# Adafruit_Audio_BFF_PCB.net
KiCad netlist of a schematic drawn in EAGLE
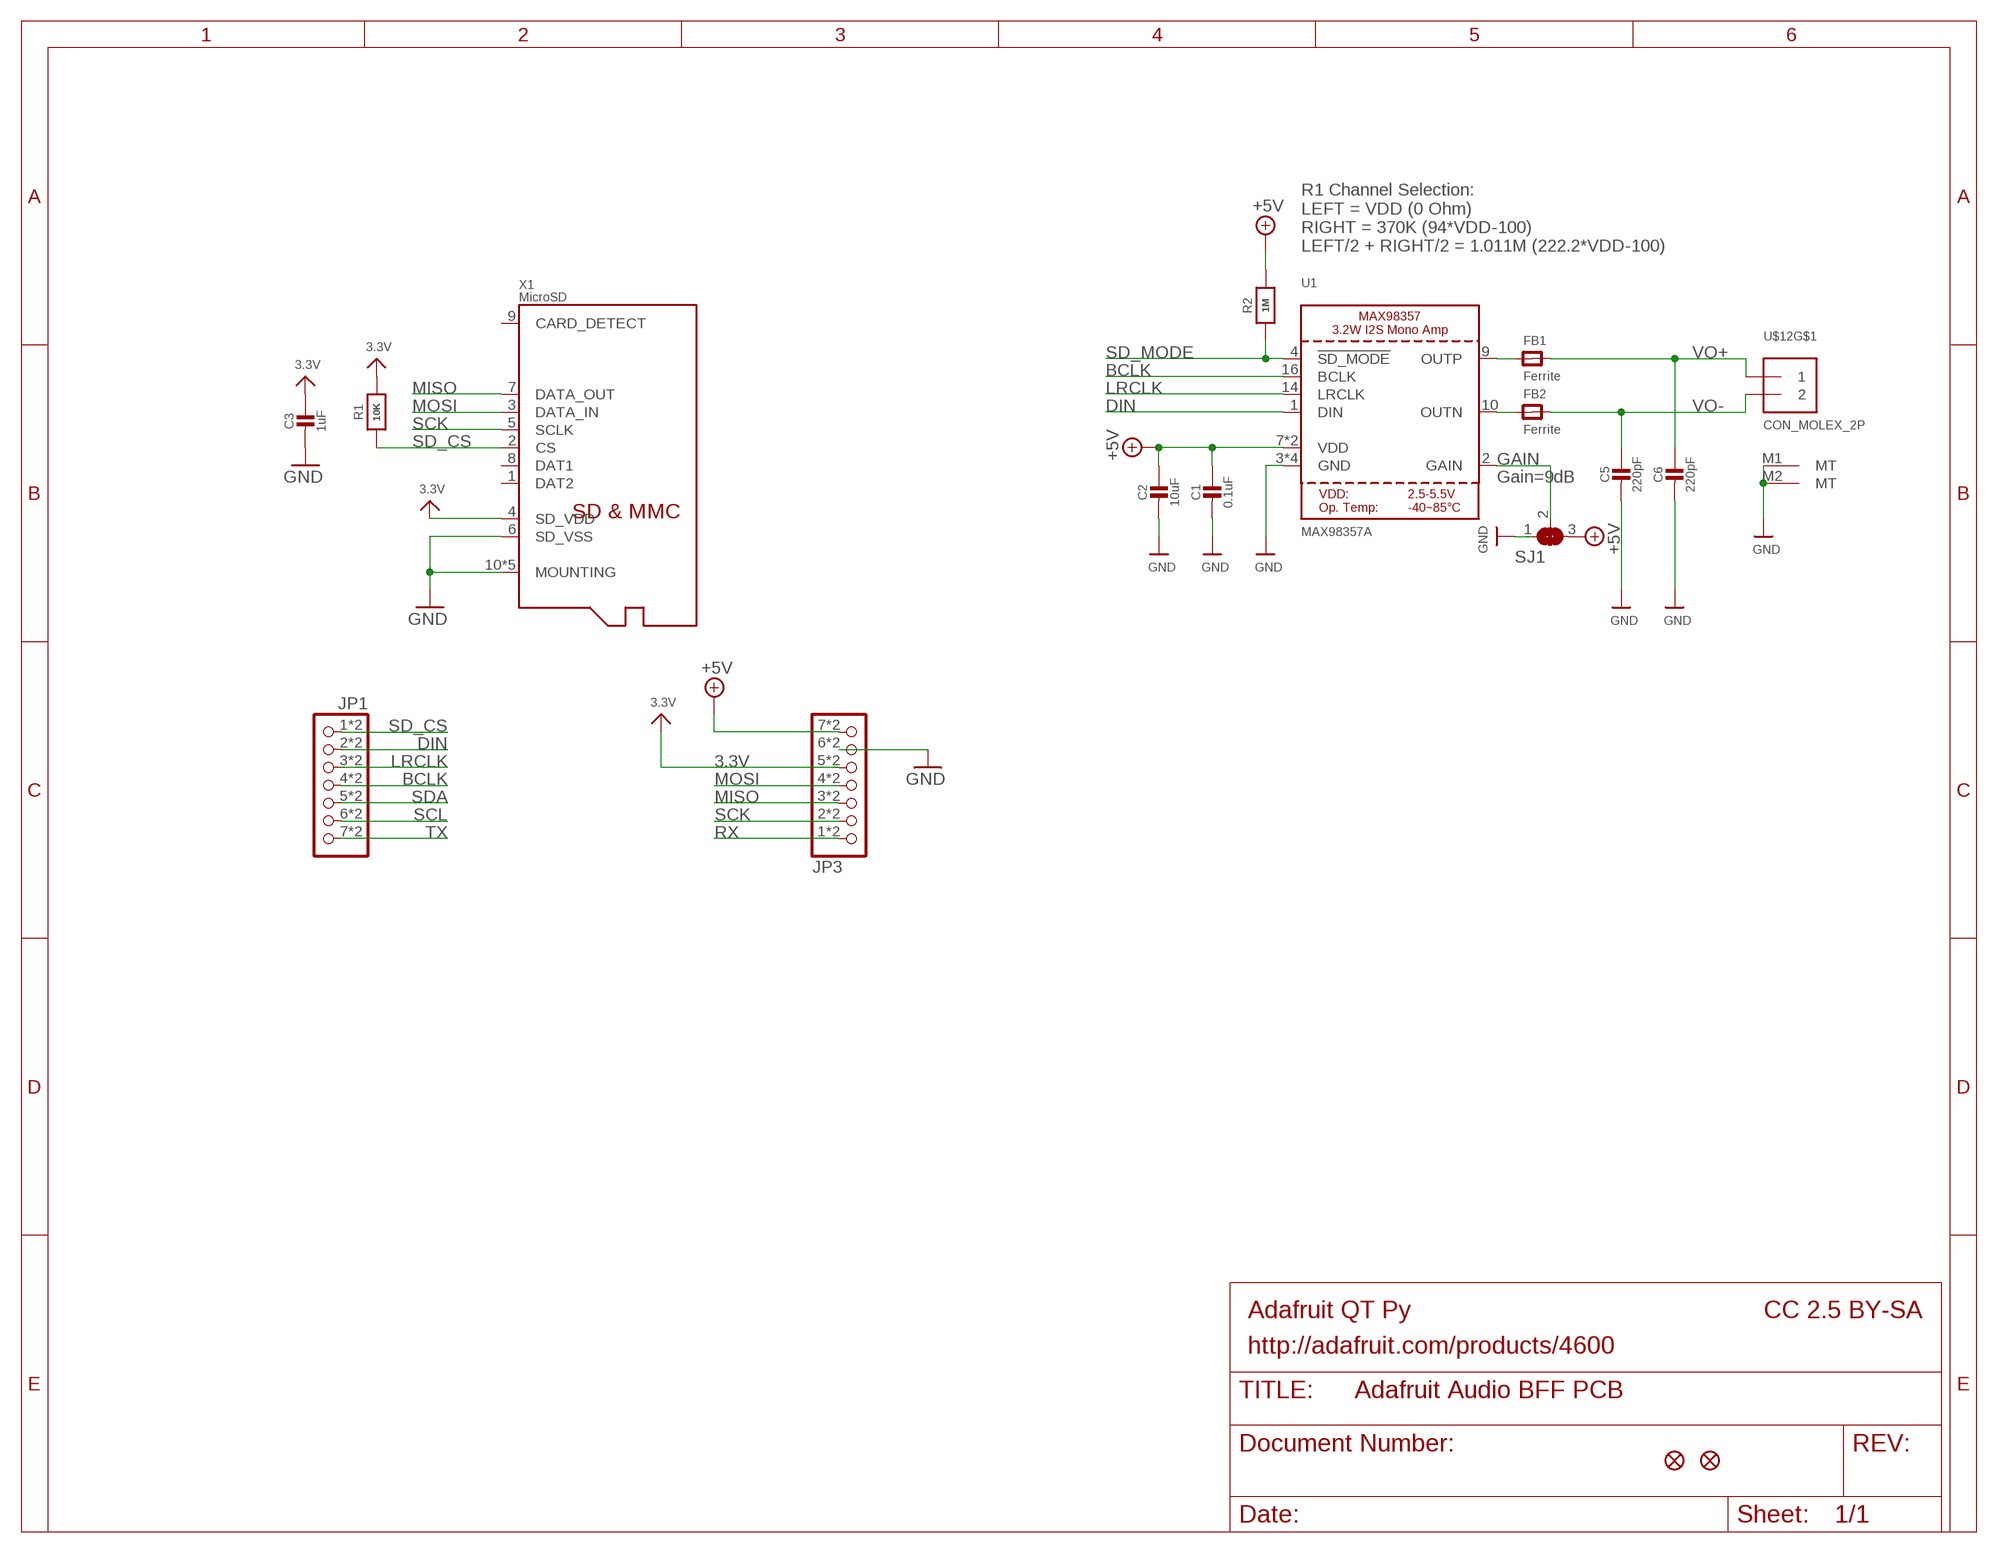
[diagram p0: schematic, sheet 1]

(export (version "E")
  (design (tool "Eeschema 10.0.6"))
  (components
    (comp (ref "C1")
      (value "0.1uF")
      (footprint "eagle-import:_0402NO")
      (libsource (lib "eagle-import") (part "CAP_CERAMIC_0402NO"))
    )
    (comp (ref "C2")
      (value "10uF")
      (footprint "eagle-import:0805-NO")
      (libsource (lib "eagle-import") (part "CAP_CERAMIC0805-NOOUTLINE"))
    )
    (comp (ref "C3")
      (value "1uF")
      (footprint "eagle-import:_0402NO")
      (libsource (lib "eagle-import") (part "CAP_CERAMIC_0402NO"))
    )
    (comp (ref "C5")
      (value "220pF")
      (footprint "eagle-import:_0402NO")
      (libsource (lib "eagle-import") (part "CAP_CERAMIC_0402NO"))
    )
    (comp (ref "C6")
      (value "220pF")
      (footprint "eagle-import:_0402NO")
      (libsource (lib "eagle-import") (part "CAP_CERAMIC_0402NO"))
    )
    (comp (ref "FB1")
      (value "Ferrite")
      (footprint "eagle-import:_0402")
      (libsource (lib "eagle-import") (part "FERRITE_0402"))
    )
    (comp (ref "FB2")
      (value "Ferrite")
      (footprint "eagle-import:_0402")
      (libsource (lib "eagle-import") (part "FERRITE_0402"))
    )
    (comp (ref "JP1")
      (value "HEADER-1X7_CASTEL")
      (footprint "eagle-import:1X07_CASTEL")
      (libsource (lib "eagle-import") (part "HEADER-1X7_CASTEL"))
    )
    (comp (ref "JP3")
      (value "HEADER-1X7_CASTEL")
      (footprint "eagle-import:1X07_CASTEL")
      (libsource (lib "eagle-import") (part "HEADER-1X7_CASTEL"))
    )
    (comp (ref "R1")
      (value "10K")
      (footprint "eagle-import:_0402NO")
      (libsource (lib "eagle-import") (part "RESISTOR_0402NO"))
    )
    (comp (ref "R2")
      (value "1M")
      (footprint "eagle-import:_0402NO")
      (libsource (lib "eagle-import") (part "RESISTOR_0402NO"))
    )
    (comp (ref "SJ1")
      (value "SOLDERJUMPER_2WAY")
      (footprint "eagle-import:SOLDERJUMPER_2WAY_OPEN_NOPASTE")
      (libsource (lib "eagle-import") (part "SOLDERJUMPER_2WAY"))
    )
    (comp (ref "U$6")
      (value "FIDUCIAL_1MM")
      (footprint "eagle-import:FIDUCIAL_1MM")
      (libsource (lib "eagle-import") (part "FIDUCIAL_1MM"))
    )
    (comp (ref "U$8")
      (value "FIDUCIAL_1MM")
      (footprint "eagle-import:FIDUCIAL_1MM")
      (libsource (lib "eagle-import") (part "FIDUCIAL_1MM"))
    )
    (comp (ref "U$12")
      (value "CON_MOLEX_2P")
      (footprint "eagle-import:53398-0271")
      (libsource (lib "eagle-import") (part "CON_MOLEX_2P"))
    )
    (comp (ref "U1")
      (value "MAX98357A")
      (footprint "eagle-import:QFN16_3MM")
      (libsource (lib "eagle-import") (part "AUDIOAMP_MAX98357"))
    )
    (comp (ref "X1")
      (value "MicroSD")
      (footprint "eagle-import:MOLEX_104031-0811")
      (libsource (lib "eagle-import") (part "MICROSD104031-0811"))
    )
  )
  (nets
    (net (code "1") (name "+5V") (class "Default")
      (node (ref "C1") (pin "1") (pinfunction "1_1") (pintype "passive"))
      (node (ref "C2") (pin "1") (pinfunction "1_1") (pintype "passive"))
      (node (ref "JP3") (pin "7") (pinfunction "7_7") (pintype "passive"))
      (node (ref "JP3") (pin "7C") (pinfunction "7_7C") (pintype "passive"))
      (node (ref "R2") (pin "2") (pinfunction "2_2") (pintype "passive"))
      (node (ref "SJ1") (pin "3") (pinfunction "3_3") (pintype "passive"))
      (node (ref "U1") (pin "7") (pinfunction "VDD_7") (pintype "power_in"))
      (node (ref "U1") (pin "8") (pinfunction "VDD_8") (pintype "power_in"))
    )
    (net (code "2") (name "/BCLK") (class "Default")
      (node (ref "JP1") (pin "4") (pinfunction "4_4") (pintype "passive"))
      (node (ref "JP1") (pin "4C") (pinfunction "4_4C") (pintype "passive"))
      (node (ref "U1") (pin "16") (pinfunction "BCLK_16") (pintype "bidirectional"))
    )
    (net (code "3") (name "/DIN") (class "Default")
      (node (ref "JP1") (pin "2") (pinfunction "2_2") (pintype "passive"))
      (node (ref "JP1") (pin "2C") (pinfunction "2_2C") (pintype "passive"))
      (node (ref "U1") (pin "1") (pinfunction "DIN_1") (pintype "bidirectional"))
    )
    (net (code "4") (name "/GAIN") (class "Default")
      (node (ref "SJ1") (pin "2") (pinfunction "2_2") (pintype "passive"))
      (node (ref "U1") (pin "2") (pinfunction "GAIN_2") (pintype "bidirectional"))
    )
    (net (code "5") (name "/LRCLK") (class "Default")
      (node (ref "JP1") (pin "3") (pinfunction "3_3") (pintype "passive"))
      (node (ref "JP1") (pin "3C") (pinfunction "3_3C") (pintype "passive"))
      (node (ref "U1") (pin "14") (pinfunction "LRCLK_14") (pintype "bidirectional"))
    )
    (net (code "6") (name "/MISO") (class "Default")
      (node (ref "JP3") (pin "3") (pinfunction "3_3") (pintype "passive"))
      (node (ref "JP3") (pin "3C") (pinfunction "3_3C") (pintype "passive"))
      (node (ref "X1") (pin "7") (pinfunction "DATA_OUT_7") (pintype "output"))
    )
    (net (code "7") (name "/MOSI") (class "Default")
      (node (ref "JP3") (pin "4") (pinfunction "4_4") (pintype "passive"))
      (node (ref "JP3") (pin "4C") (pinfunction "4_4C") (pintype "passive"))
      (node (ref "X1") (pin "3") (pinfunction "DATA_IN_3") (pintype "input"))
    )
    (net (code "8") (name "/RX") (class "Default")
      (node (ref "JP3") (pin "1") (pinfunction "1_1") (pintype "passive"))
      (node (ref "JP3") (pin "1C") (pinfunction "1_1C") (pintype "passive"))
    )
    (net (code "9") (name "/SCK") (class "Default")
      (node (ref "JP3") (pin "2") (pinfunction "2_2") (pintype "passive"))
      (node (ref "JP3") (pin "2C") (pinfunction "2_2C") (pintype "passive"))
      (node (ref "X1") (pin "5") (pinfunction "SCLK_5") (pintype "input"))
    )
    (net (code "10") (name "/SCL") (class "Default")
      (node (ref "JP1") (pin "6") (pinfunction "6_6") (pintype "passive"))
      (node (ref "JP1") (pin "6C") (pinfunction "6_6C") (pintype "passive"))
    )
    (net (code "11") (name "/SDA") (class "Default")
      (node (ref "JP1") (pin "5") (pinfunction "5_5") (pintype "passive"))
      (node (ref "JP1") (pin "5C") (pinfunction "5_5C") (pintype "passive"))
    )
    (net (code "12") (name "/SD_CS") (class "Default")
      (node (ref "JP1") (pin "1") (pinfunction "1_1") (pintype "passive"))
      (node (ref "JP1") (pin "1C") (pinfunction "1_1C") (pintype "passive"))
      (node (ref "R1") (pin "1") (pinfunction "1_1") (pintype "passive"))
      (node (ref "X1") (pin "2") (pinfunction "CS_2") (pintype "input"))
    )
    (net (code "13") (name "/SD_MODE") (class "Default")
      (node (ref "R2") (pin "1") (pinfunction "1_1") (pintype "passive"))
      (node (ref "U1") (pin "4") (pinfunction "~{SD_MODE}_4") (pintype "bidirectional"))
    )
    (net (code "14") (name "/TX") (class "Default")
      (node (ref "JP1") (pin "7") (pinfunction "7_7") (pintype "passive"))
      (node (ref "JP1") (pin "7C") (pinfunction "7_7C") (pintype "passive"))
    )
    (net (code "15") (name "/VO+") (class "Default")
      (node (ref "C6") (pin "1") (pinfunction "1_1") (pintype "passive"))
      (node (ref "FB1") (pin "2") (pinfunction "P$2_2") (pintype "passive"))
      (node (ref "U$12") (pin "1") (pinfunction "1_1") (pintype "passive"))
    )
    (net (code "16") (name "/VO-") (class "Default")
      (node (ref "C5") (pin "1") (pinfunction "1_1") (pintype "passive"))
      (node (ref "FB2") (pin "2") (pinfunction "P$2_2") (pintype "passive"))
      (node (ref "U$12") (pin "2") (pinfunction "2_2") (pintype "passive"))
    )
    (net (code "17") (name "3.3V") (class "Default")
      (node (ref "C3") (pin "1") (pinfunction "1_1") (pintype "passive"))
      (node (ref "JP3") (pin "5") (pinfunction "5_5") (pintype "passive"))
      (node (ref "JP3") (pin "5C") (pinfunction "5_5C") (pintype "passive"))
      (node (ref "R1") (pin "2") (pinfunction "2_2") (pintype "passive"))
      (node (ref "X1") (pin "4") (pinfunction "SD_VDD_4") (pintype "power_in"))
    )
    (net (code "18") (name "GND") (class "Default")
      (node (ref "C1") (pin "2") (pinfunction "2_2") (pintype "passive"))
      (node (ref "C2") (pin "2") (pinfunction "2_2") (pintype "passive"))
      (node (ref "C3") (pin "2") (pinfunction "2_2") (pintype "passive"))
      (node (ref "C5") (pin "2") (pinfunction "2_2") (pintype "passive"))
      (node (ref "C6") (pin "2") (pinfunction "2_2") (pintype "passive"))
      (node (ref "JP3") (pin "6") (pinfunction "6_6") (pintype "passive"))
      (node (ref "JP3") (pin "6C") (pinfunction "6_6C") (pintype "passive"))
      (node (ref "SJ1") (pin "1") (pinfunction "1_1") (pintype "passive"))
      (node (ref "U$12") (pin "M1") (pinfunction "MT_M1") (pintype "bidirectional"))
      (node (ref "U$12") (pin "M2") (pinfunction "MT_M2") (pintype "bidirectional"))
      (node (ref "U1") (pin "11") (pinfunction "GND_11") (pintype "power_in"))
      (node (ref "U1") (pin "15") (pinfunction "GND_15") (pintype "power_in"))
      (node (ref "U1") (pin "3") (pinfunction "GND_3") (pintype "power_in"))
      (node (ref "U1") (pin "THERMAL") (pinfunction "GND_THERMAL") (pintype "power_in"))
      (node (ref "X1") (pin "10") (pinfunction "MOUNTING_10") (pintype "passive"))
      (node (ref "X1") (pin "6") (pinfunction "SD_VSS_6") (pintype "power_in"))
      (node (ref "X1") (pin "G1") (pinfunction "MOUNTING_G1") (pintype "passive"))
      (node (ref "X1") (pin "G2") (pinfunction "MOUNTING_G2") (pintype "passive"))
      (node (ref "X1") (pin "G3") (pinfunction "MOUNTING_G3") (pintype "passive"))
      (node (ref "X1") (pin "G4") (pinfunction "MOUNTING_G4") (pintype "passive"))
    )
    (net (code "19") (name "Net-(FB1-P$1)") (class "Default")
      (node (ref "FB1") (pin "1") (pinfunction "P$1_1") (pintype "passive"))
      (node (ref "U1") (pin "9") (pinfunction "OUTP_9") (pintype "output"))
    )
    (net (code "20") (name "Net-(FB2-P$1)") (class "Default")
      (node (ref "FB2") (pin "1") (pinfunction "P$1_1") (pintype "passive"))
      (node (ref "U1") (pin "10") (pinfunction "OUTN_10") (pintype "output"))
    )
    (net (code "21") (name "unconnected-(X1-CARD_DETECT-Pad9)") (class "Default")
      (node (ref "X1") (pin "9") (pinfunction "CARD_DETECT_9") (pintype "passive"))
    )
    (net (code "22") (name "unconnected-(X1-DAT1-Pad8)") (class "Default")
      (node (ref "X1") (pin "8") (pinfunction "DAT1_8") (pintype "bidirectional"))
    )
    (net (code "23") (name "unconnected-(X1-DAT2-Pad1)") (class "Default")
      (node (ref "X1") (pin "1") (pinfunction "DAT2_1") (pintype "bidirectional"))
    )
  )
)
